# T32_ref.net
KiCad netlist of a schematic drawn in EAGLE
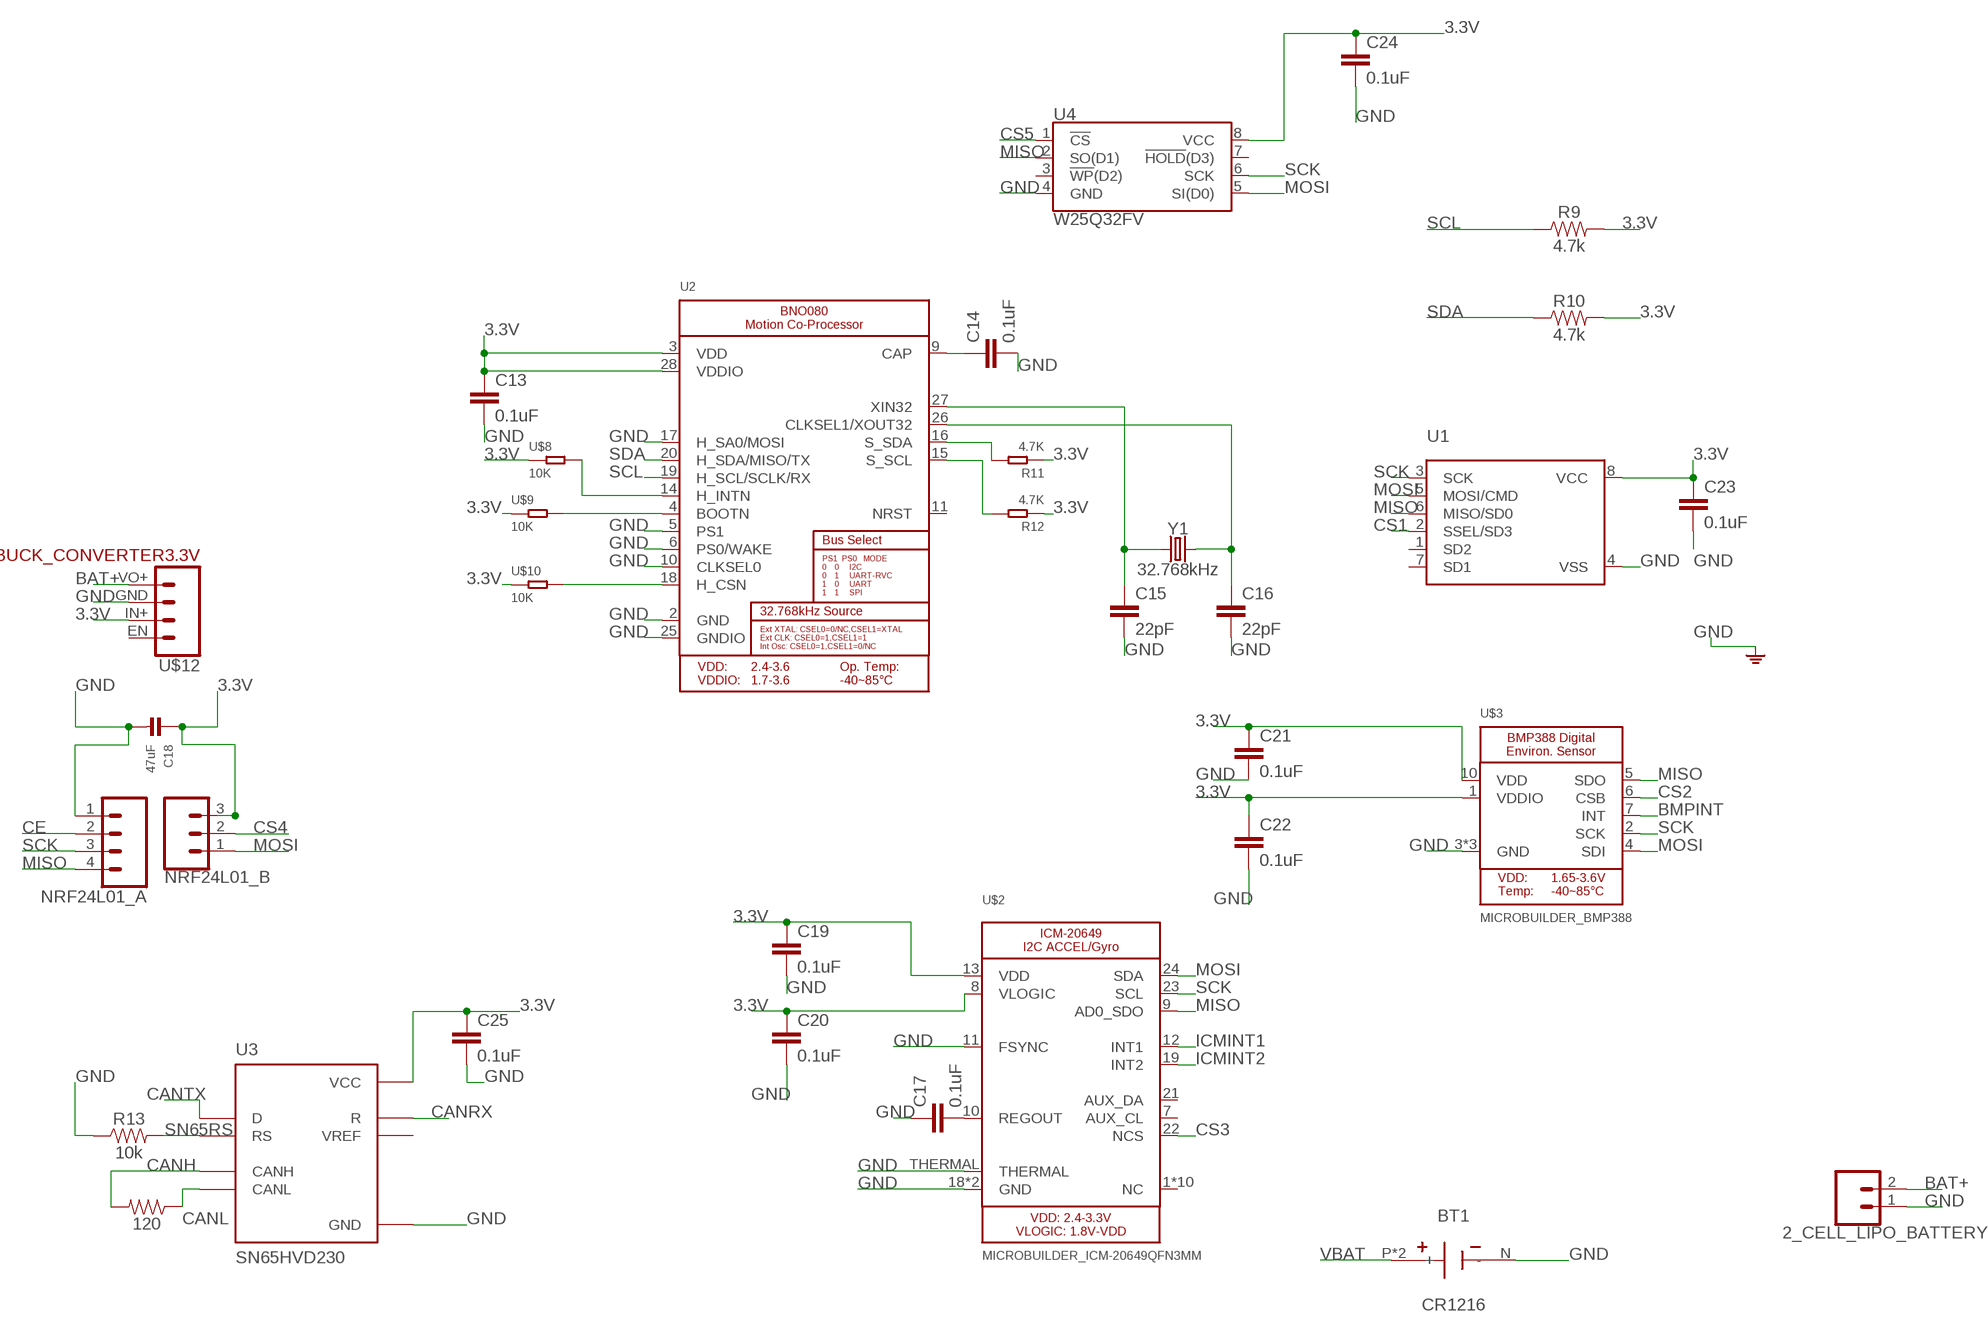
[diagram p0: schematic, sheet 1, part 1 of 2]
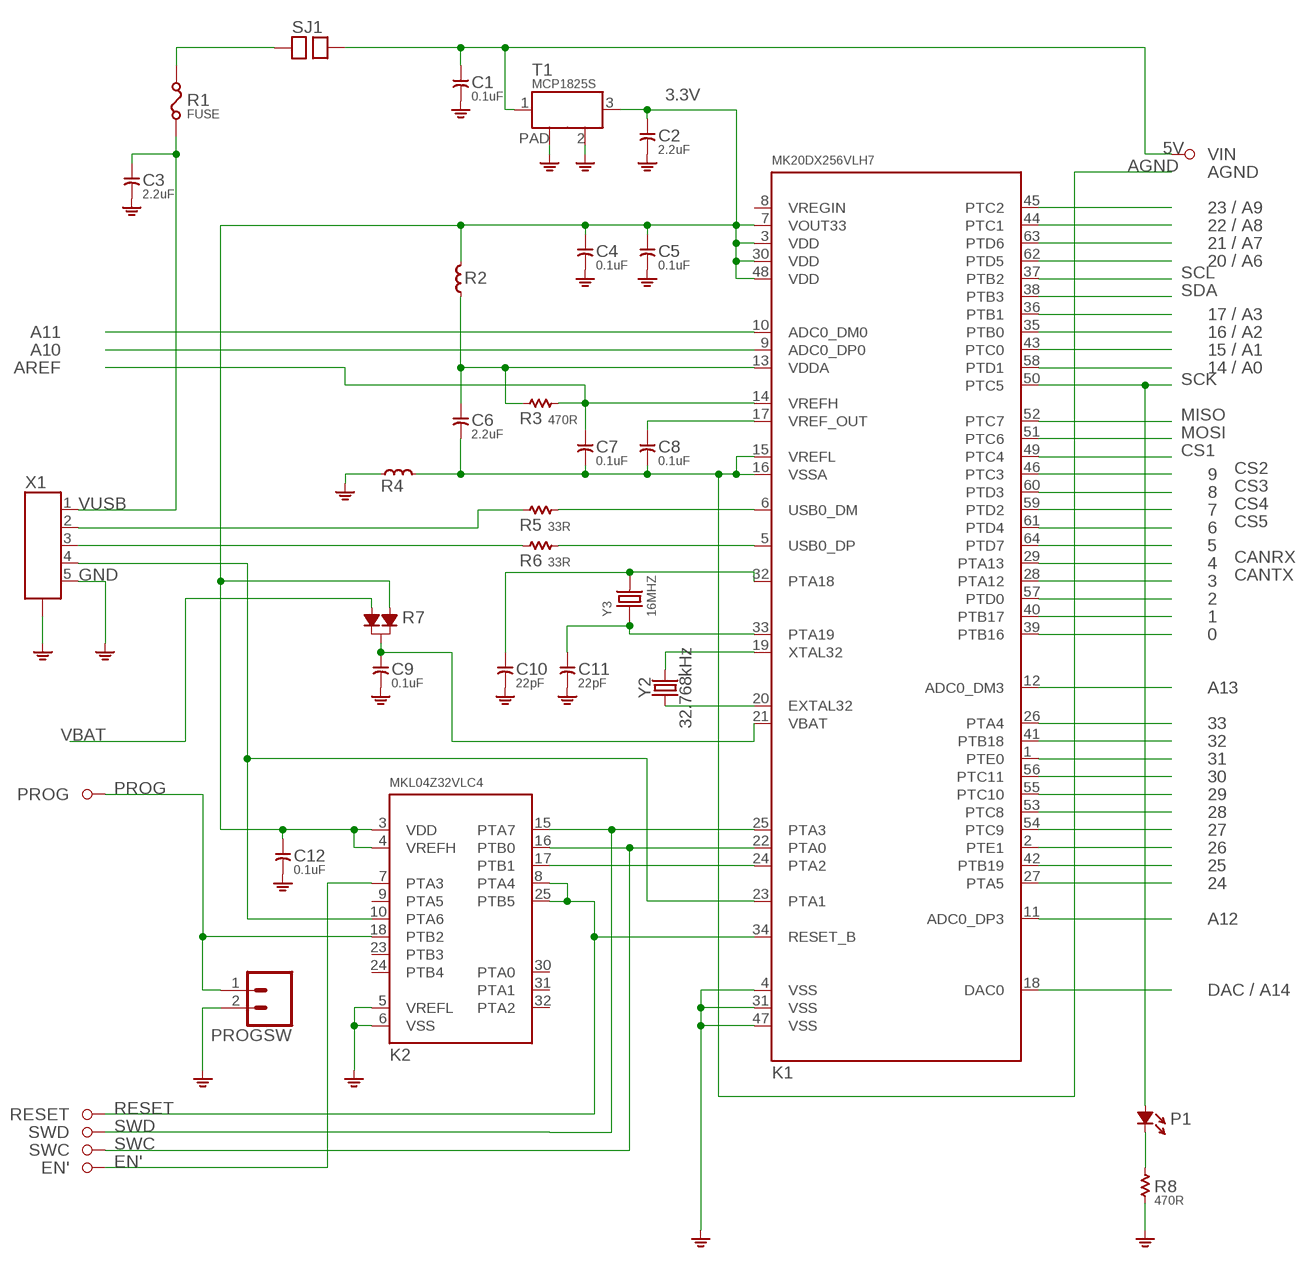
[diagram p1: schematic, sheet 1, part 2 of 2]

(export (version "E")
  (design (tool "Eeschema 10.0.6"))
  (components
    (comp (ref "2_CELL_LIPO_BATTERY")
      (value "CONN_02")
      (footprint "eagle-import:1X02")
      (libsource (lib "eagle-import") (part "CONN_02"))
    )
    (comp (ref "120")
      (value "RESISTOR1206")
      (footprint "eagle-import:1206")
      (libsource (lib "eagle-import") (part "RESISTOR1206"))
    )
    (comp (ref "BT1")
      (value "CR1216")
      (footprint "eagle-import:BAT_3000")
      (fields (field (name "MANUFACTURER") "Keystone Electronics") (field (name "MPN") "3000"))
      (libsource (lib "eagle-import") (part "COIN-CELL-SMT-3P-?-3000CR1216"))
    )
    (comp (ref "C1")
      (value "0.1uF")
      (footprint "eagle-import:C0603")
      (fields (field (name "MF") "Murata Electronics") (field (name "MPN") "GRM188R71C104KA01D"))
      (libsource (lib "eagle-import") (part "CAPACITOR-0.1UF"))
    )
    (comp (ref "C2")
      (value "2.2uF")
      (footprint "eagle-import:C0805")
      (fields (field (name "MF") "Taiyo Yuden") (field (name "MPN") "TMK212B7225KG-TR"))
      (libsource (lib "eagle-import") (part "CAPACITOR-2.2UF"))
    )
    (comp (ref "C3")
      (value "2.2uF")
      (footprint "eagle-import:C0805")
      (fields (field (name "MF") "Taiyo Yuden") (field (name "MPN") "TMK212B7225KG-TR"))
      (libsource (lib "eagle-import") (part "CAPACITOR-2.2UF"))
    )
    (comp (ref "C4")
      (value "0.1uF")
      (footprint "eagle-import:C0603")
      (fields (field (name "MF") "Murata Electronics") (field (name "MPN") "GRM188R71C104KA01D"))
      (libsource (lib "eagle-import") (part "CAPACITOR-0.1UF"))
    )
    (comp (ref "C5")
      (value "0.1uF")
      (footprint "eagle-import:C0603")
      (fields (field (name "MF") "Murata Electronics") (field (name "MPN") "GRM188R71C104KA01D"))
      (libsource (lib "eagle-import") (part "CAPACITOR-0.1UF"))
    )
    (comp (ref "C6")
      (value "2.2uF")
      (footprint "eagle-import:C0805")
      (fields (field (name "MF") "Taiyo Yuden") (field (name "MPN") "TMK212B7225KG-TR"))
      (libsource (lib "eagle-import") (part "CAPACITOR-2.2UF"))
    )
    (comp (ref "C7")
      (value "0.1uF")
      (footprint "eagle-import:C0603")
      (fields (field (name "MF") "Murata Electronics") (field (name "MPN") "GRM188R71C104KA01D"))
      (libsource (lib "eagle-import") (part "CAPACITOR-0.1UF"))
    )
    (comp (ref "C8")
      (value "0.1uF")
      (footprint "eagle-import:C0603")
      (fields (field (name "MF") "Murata Electronics") (field (name "MPN") "GRM188R71C104KA01D"))
      (libsource (lib "eagle-import") (part "CAPACITOR-0.1UF"))
    )
    (comp (ref "C9")
      (value "0.1uF")
      (footprint "eagle-import:C0603")
      (fields (field (name "MF") "Murata Electronics") (field (name "MPN") "GRM188R71C104KA01D"))
      (libsource (lib "eagle-import") (part "CAPACITOR-0.1UF"))
    )
    (comp (ref "C10")
      (value "22pF")
      (footprint "eagle-import:C0603")
      (fields (field (name "MF") "Vishay / Vitramon") (field (name "MPN") "VJ0603A220JXACW1BC"))
      (libsource (lib "eagle-import") (part "CAPACITOR-22PF"))
    )
    (comp (ref "C11")
      (value "22pF")
      (footprint "eagle-import:C0603")
      (fields (field (name "MF") "Vishay / Vitramon") (field (name "MPN") "VJ0603A220JXACW1BC"))
      (libsource (lib "eagle-import") (part "CAPACITOR-22PF"))
    )
    (comp (ref "C12")
      (value "0.1uF")
      (footprint "eagle-import:C0603")
      (fields (field (name "MF") "Murata Electronics") (field (name "MPN") "GRM188R71C104KA01D"))
      (libsource (lib "eagle-import") (part "CAPACITOR-0.1UF"))
    )
    (comp (ref "C13")
      (value "0.1uF")
      (footprint "eagle-import:0402")
      (libsource (lib "eagle-import") (part "0.1UF-0402-16V-10%"))
    )
    (comp (ref "C14")
      (value "0.1uF")
      (footprint "eagle-import:0402")
      (libsource (lib "eagle-import") (part "0.1UF-0402-16V-10%"))
    )
    (comp (ref "C15")
      (value "22pF")
      (footprint "eagle-import:0603")
      (libsource (lib "eagle-import") (part "22PF-0603-50V-5%"))
    )
    (comp (ref "C16")
      (value "22pF")
      (footprint "eagle-import:0603")
      (libsource (lib "eagle-import") (part "22PF-0603-50V-5%"))
    )
    (comp (ref "C17")
      (value "0.1uF")
      (footprint "eagle-import:0402")
      (libsource (lib "eagle-import") (part "0.1UF-0402-16V-10%"))
    )
    (comp (ref "C18")
      (value "47uF")
      (footprint "eagle-import:0805")
      (libsource (lib "eagle-import") (part "CAP_CERAMIC0805"))
    )
    (comp (ref "C19")
      (value "0.1uF")
      (footprint "eagle-import:0603")
      (libsource (lib "eagle-import") (part "0.1UF-0603-100V-10%"))
    )
    (comp (ref "C20")
      (value "0.1uF")
      (footprint "eagle-import:0603")
      (libsource (lib "eagle-import") (part "0.1UF-0603-100V-10%"))
    )
    (comp (ref "C21")
      (value "0.1uF")
      (footprint "eagle-import:0603")
      (libsource (lib "eagle-import") (part "0.1UF-0603-100V-10%"))
    )
    (comp (ref "C22")
      (value "0.1uF")
      (footprint "eagle-import:0603")
      (libsource (lib "eagle-import") (part "0.1UF-0603-100V-10%"))
    )
    (comp (ref "C23")
      (value "0.1uF")
      (footprint "eagle-import:0603")
      (libsource (lib "eagle-import") (part "0.1UF-0603-100V-10%"))
    )
    (comp (ref "C24")
      (value "0.1uF")
      (footprint "eagle-import:0603")
      (libsource (lib "eagle-import") (part "0.1UF-0603-100V-10%"))
    )
    (comp (ref "C25")
      (value "0.1uF")
      (footprint "eagle-import:0603")
      (libsource (lib "eagle-import") (part "0.1UF-0603-100V-10%"))
    )
    (comp (ref "K1")
      (value "MK20DX256VLH7")
      (footprint "eagle-import:LQFP64-05")
      (fields (field (name "MF") "NXP"))
      (libsource (lib "eagle-import") (part "MK20DX256VLH7"))
    )
    (comp (ref "K2")
      (value "MKL04Z32VLC4")
      (footprint "eagle-import:LQFP32-08")
      (fields (field (name "MF") "PJRC") (field (name "MPN") "IC_MKL04Z32_TQFP32"))
      (libsource (lib "eagle-import") (part "MKL04Z32VLC4"))
    )
    (comp (ref "NRF24L01_A")
      (value "CONN_04")
      (footprint "eagle-import:1X04")
      (libsource (lib "eagle-import") (part "CONN_04"))
    )
    (comp (ref "NRF24L01_B")
      (value "CONN_03")
      (footprint "eagle-import:1X03")
      (libsource (lib "eagle-import") (part "CONN_03"))
    )
    (comp (ref "P1")
      (value "LED")
      (footprint "eagle-import:LED-0805")
      (fields (field (name "MF") "ROHM Semiconductor") (field (name "MPN") "SML-211DTT86"))
      (libsource (lib "eagle-import") (part "LED"))
    )
    (comp (ref "PROGSW")
      (value "CONN_02")
      (footprint "eagle-import:1X02")
      (libsource (lib "eagle-import") (part "SparkFun-Connectors_513_CONN_02"))
    )
    (comp (ref "R1")
      (value "FUSE")
      (footprint "eagle-import:F0805")
      (fields (field (name "MF") "Bel Fuse") (field (name "MPN") "0ZCK0050FF2E"))
      (libsource (lib "eagle-import") (part "FUSE"))
    )
    (comp (ref "R2")
      (value "FERRITE")
      (footprint "eagle-import:L0603")
      (fields (field (name "MF") "Murata Electronics") (field (name "MPN") " BLM18AG601SN1D"))
      (libsource (lib "eagle-import") (part "FERRITE"))
    )
    (comp (ref "R3")
      (value "470R")
      (footprint "eagle-import:R0603")
      (fields (field (name "MF") "Vishay") (field (name "MPN") "CRCW0603470RFKEA"))
      (libsource (lib "eagle-import") (part "RESISTOR-470R"))
    )
    (comp (ref "R4")
      (value "FERRITE")
      (footprint "eagle-import:L0603")
      (fields (field (name "MF") "Murata Electronics") (field (name "MPN") " BLM18AG601SN1D"))
      (libsource (lib "eagle-import") (part "FERRITE"))
    )
    (comp (ref "R5")
      (value "33R")
      (footprint "eagle-import:R0603")
      (fields (field (name "MF") "Panasonic") (field (name "MPN") "ERJ-PA3F33R0V"))
      (libsource (lib "eagle-import") (part "RESISTOR-33R"))
    )
    (comp (ref "R6")
      (value "33R")
      (footprint "eagle-import:R0603")
      (fields (field (name "MF") "Panasonic") (field (name "MPN") "ERJ-PA3F33R0V"))
      (libsource (lib "eagle-import") (part "RESISTOR-33R"))
    )
    (comp (ref "R7")
      (value "DIODE_DUAL")
      (footprint "eagle-import:SOT-23")
      (fields (field (name "MF") "NXP Semiconductors") (field (name "MPN") "BAT54C,215"))
      (libsource (lib "eagle-import") (part "DIODE_DUAL"))
    )
    (comp (ref "R8")
      (value "470R")
      (footprint "eagle-import:R0603")
      (fields (field (name "MF") "Vishay") (field (name "MPN") "CRCW0603470RFKEA"))
      (libsource (lib "eagle-import") (part "RESISTOR-470R"))
    )
    (comp (ref "R9")
      (value "4.7k")
      (footprint "eagle-import:0603")
      (libsource (lib "eagle-import") (part "4.7KOHM-0603-1/10W-1%"))
    )
    (comp (ref "R10")
      (value "4.7k")
      (footprint "eagle-import:0603")
      (libsource (lib "eagle-import") (part "4.7KOHM-0603-1/10W-1%"))
    )
    (comp (ref "R11")
      (value "4.7K")
      (footprint "eagle-import:R0402")
      (fields (field (name "MPN") "RC0402JR-074K7L"))
      (libsource (lib "eagle-import") (part "SMD-RES-4.7K-5%-1/16W(0402)"))
    )
    (comp (ref "R12")
      (value "4.7K")
      (footprint "eagle-import:R0402")
      (fields (field (name "MPN") "RC0402JR-074K7L"))
      (libsource (lib "eagle-import") (part "SMD-RES-4.7K-5%-1/16W(0402)"))
    )
    (comp (ref "R13")
      (value "10k")
      (footprint "eagle-import:0603")
      (libsource (lib "eagle-import") (part "10KOHM-0603-1/10W-1%"))
    )
    (comp (ref "SJ1")
      (value "SOLDERJUMPER")
      (footprint "eagle-import:SOLDERJUMPER")
      (libsource (lib "eagle-import") (part "SOLDERJUMPER"))
    )
    (comp (ref "SX2")
      (value "PIN")
      (footprint "eagle-import:PTH_39MIL")
      (libsource (lib "eagle-import") (part "PIN"))
    )
    (comp (ref "SX38")
      (value "PIN")
      (footprint "eagle-import:PTH_39MIL")
      (libsource (lib "eagle-import") (part "PIN"))
    )
    (comp (ref "SX40")
      (value "PIN")
      (footprint "eagle-import:PTH_39MIL")
      (libsource (lib "eagle-import") (part "PIN"))
    )
    (comp (ref "SX57")
      (value "PIN")
      (footprint "eagle-import:PTH_39MIL")
      (libsource (lib "eagle-import") (part "PIN"))
    )
    (comp (ref "SX58")
      (value "PIN")
      (footprint "eagle-import:PTH_39MIL")
      (libsource (lib "eagle-import") (part "PIN"))
    )
    (comp (ref "SX59")
      (value "PIN")
      (footprint "eagle-import:PTH_39MIL")
      (libsource (lib "eagle-import") (part "PIN"))
    )
    (comp (ref "T1")
      (value "MCP1825S")
      (footprint "eagle-import:SOT-223")
      (fields (field (name "MF") "Microchip Technology") (field (name "MPN") "MCP1825S-3302E/DB"))
      (libsource (lib "eagle-import") (part "LDO"))
    )
    (comp (ref "U$2")
      (value "MICROBUILDER_ICM-20649QFN3MM")
      (footprint "eagle-import:MICROBUILDER_QFN24_3MM")
      (libsource (lib "eagle-import") (part "MICROBUILDER_ICM-20649QFN3MM"))
    )
    (comp (ref "U$3")
      (value "MICROBUILDER_BMP388")
      (footprint "eagle-import:MICROBUILDER_BMP388")
      (libsource (lib "eagle-import") (part "MICROBUILDER_BMP388"))
    )
    (comp (ref "U$8")
      (value "10K")
      (footprint "eagle-import:R0402")
      (fields (field (name "MPN") "RC0402JR-0710KL"))
      (libsource (lib "eagle-import") (part "SMD-RES-10K-5%-1/(0402)"))
    )
    (comp (ref "U$9")
      (value "10K")
      (footprint "eagle-import:R0402")
      (fields (field (name "MPN") "RC0402JR-0710KL"))
      (libsource (lib "eagle-import") (part "SMD-RES-10K-5%-1/(0402)"))
    )
    (comp (ref "U$10")
      (value "10K")
      (footprint "eagle-import:R0402")
      (fields (field (name "MPN") "RC0402JR-0710KL"))
      (libsource (lib "eagle-import") (part "SMD-RES-10K-5%-1/(0402)"))
    )
    (comp (ref "U$12")
      (value "BUCK_CONVERTER3.3V")
      (footprint "eagle-import:1X04")
      (fields (field (name "VOLTAGE") "3.3V"))
      (libsource (lib "eagle-import") (part "BUCK_CONVERTER3.3V"))
    )
    (comp (ref "U1")
      (value "MICROBUILDER_SMT_SDCARD_8PIN")
      (footprint "eagle-import:MICROBUILDER_LGA8_8X6")
      (libsource (lib "eagle-import") (part "MICROBUILDER_SMT_SDCARD_8PIN"))
    )
    (comp (ref "U2")
      (value "MICROBUILDER_BNO080")
      (footprint "eagle-import:MICROBUILDER_BNO080")
      (libsource (lib "eagle-import") (part "MICROBUILDER_BNO080"))
    )
    (comp (ref "U3")
      (value "SN65HVD230")
      (footprint "eagle-import:SOIC127P599X175-8N")
      (fields (field (name "MF") "Texas Instruments"))
      (libsource (lib "eagle-import") (part "SN65HVD230"))
    )
    (comp (ref "U4")
      (value "W25Q32FV")
      (footprint "eagle-import:WSON8-6X5MM")
      (libsource (lib "eagle-import") (part "W25Q32FVZP"))
    )
    (comp (ref "X1")
      (value "MINI-USB")
      (footprint "eagle-import:MOLEX_SD-67503-010")
      (fields (field (name "MF") "MOLEX") (field (name "MPN") "0675031020"))
      (libsource (lib "eagle-import") (part "MINI-USBMOLEX_0675031230"))
    )
    (comp (ref "Y1")
      (value "32.768kHz")
      (footprint "eagle-import:CRYSTAL-SMD-3.2X1.5MM")
      (libsource (lib "eagle-import") (part "CRYSTAL-32.768KHZSMD-3.2X1.5"))
    )
    (comp (ref "Y2")
      (value "32.768kHz")
      (footprint "eagle-import:CRYSTAL-SMD-3.2X1.5MM")
      (libsource (lib "eagle-import") (part "CRYSTAL-32.768KHZSMD-3.2X1.5"))
    )
    (comp (ref "Y3")
      (value "16MHZ")
      (footprint "eagle-import:X2-SMD-5.0X3.2X1.3MM")
      (fields (field (name "MPN") "X053201602002"))
      (libsource (lib "eagle-import") (part "SMD-CRYSTAL-16MHZ-8PF-20PPM-40R(2P-5.0X3.2MM)"))
    )
  )
  (nets
    (net (code "1") (name "/3.3V") (class "Default")
      (node (ref "C12") (pin "1") (pinfunction "1_1") (pintype "passive"))
      (node (ref "C13") (pin "1") (pinfunction "1_1") (pintype "passive"))
      (node (ref "C18") (pin "1") (pinfunction "P$1_1") (pintype "passive"))
      (node (ref "C19") (pin "1") (pinfunction "1_1") (pintype "passive"))
      (node (ref "C2") (pin "1") (pinfunction "1_1") (pintype "passive"))
      (node (ref "C20") (pin "1") (pinfunction "1_1") (pintype "passive"))
      (node (ref "C21") (pin "1") (pinfunction "1_1") (pintype "passive"))
      (node (ref "C22") (pin "1") (pinfunction "1_1") (pintype "passive"))
      (node (ref "C23") (pin "1") (pinfunction "1_1") (pintype "passive"))
      (node (ref "C24") (pin "1") (pinfunction "1_1") (pintype "passive"))
      (node (ref "C25") (pin "1") (pinfunction "1_1") (pintype "passive"))
      (node (ref "C4") (pin "1") (pinfunction "1_1") (pintype "passive"))
      (node (ref "C5") (pin "1") (pinfunction "1_1") (pintype "passive"))
      (node (ref "K1") (pin "3") (pinfunction "VDD_3") (pintype "bidirectional"))
      (node (ref "K1") (pin "30") (pinfunction "VDD_30") (pintype "bidirectional"))
      (node (ref "K1") (pin "48") (pinfunction "VDD_48") (pintype "bidirectional"))
      (node (ref "K1") (pin "7") (pinfunction "VOUT33_7") (pintype "bidirectional"))
      (node (ref "K2") (pin "3") (pinfunction "VDD_3") (pintype "bidirectional"))
      (node (ref "K2") (pin "4") (pinfunction "VREFH_4") (pintype "bidirectional"))
      (node (ref "NRF24L01_B") (pin "3") (pinfunction "3_3") (pintype "passive"))
      (node (ref "R10") (pin "2") (pinfunction "2_2") (pintype "passive"))
      (node (ref "R11") (pin "1") (pinfunction "1_1") (pintype "passive"))
      (node (ref "R12") (pin "1") (pinfunction "1_1") (pintype "passive"))
      (node (ref "R2") (pin "2") (pinfunction "2_2") (pintype "passive"))
      (node (ref "R7") (pin "1") (pinfunction "1_1") (pintype "bidirectional"))
      (node (ref "R9") (pin "2") (pinfunction "2_2") (pintype "passive"))
      (node (ref "T1") (pin "3") (pinfunction "OUT_3") (pintype "bidirectional"))
      (node (ref "U$10") (pin "1") (pinfunction "1_1") (pintype "passive"))
      (node (ref "U$12") (pin "IN+") (pinfunction "IN+_IN+") (pintype "passive"))
      (node (ref "U$2") (pin "13") (pinfunction "VDD_13") (pintype "power_in"))
      (node (ref "U$2") (pin "8") (pinfunction "VLOGIC_8") (pintype "power_in"))
      (node (ref "U$3") (pin "1") (pinfunction "VDDIO_1") (pintype "power_in"))
      (node (ref "U$3") (pin "10") (pinfunction "VDD_10") (pintype "power_in"))
      (node (ref "U$8") (pin "1") (pinfunction "1_1") (pintype "passive"))
      (node (ref "U$9") (pin "1") (pinfunction "1_1") (pintype "passive"))
      (node (ref "U1") (pin "8") (pinfunction "VCC_8") (pintype "power_in"))
      (node (ref "U2") (pin "28") (pinfunction "VDDIO_28") (pintype "power_in"))
      (node (ref "U2") (pin "3") (pinfunction "VDD_3") (pintype "power_in"))
      (node (ref "U3") (pin "3") (pinfunction "VCC_3") (pintype "power_in"))
      (node (ref "U4") (pin "8") (pinfunction "VCC_8") (pintype "bidirectional"))
    )
    (net (code "2") (name "/5V") (class "Default")
      (node (ref "C1") (pin "1") (pinfunction "1_1") (pintype "passive"))
      (node (ref "R1") (pin "2") (pinfunction "2_2") (pintype "bidirectional"))
      (node (ref "SJ1") (pin "1") (pinfunction "1_1") (pintype "passive"))
      (node (ref "SJ1") (pin "2") (pinfunction "2_2") (pintype "passive"))
      (node (ref "SX2") (pin "1") (pinfunction "P$1_1") (pintype "bidirectional"))
      (node (ref "T1") (pin "1") (pinfunction "IN_1") (pintype "bidirectional"))
    )
    (net (code "3") (name "/AGND") (class "Default")
      (node (ref "C6") (pin "2") (pinfunction "2_2") (pintype "passive"))
      (node (ref "C7") (pin "2") (pinfunction "2_2") (pintype "passive"))
      (node (ref "C8") (pin "2") (pinfunction "2_2") (pintype "passive"))
      (node (ref "K1") (pin "15") (pinfunction "VREFL_15") (pintype "bidirectional"))
      (node (ref "K1") (pin "16") (pinfunction "VSSA_16") (pintype "bidirectional"))
      (node (ref "R4") (pin "2") (pinfunction "2_2") (pintype "passive"))
    )
    (net (code "4") (name "/BAT+") (class "Default")
      (node (ref "2_CELL_LIPO_BATTERY") (pin "2") (pinfunction "2_2") (pintype "passive"))
      (node (ref "U$12") (pin "VO+") (pinfunction "VO+_VO+") (pintype "passive"))
    )
    (net (code "5") (name "/BMPINT") (class "Default")
      (node (ref "U$3") (pin "7") (pinfunction "INT_7") (pintype "output"))
    )
    (net (code "6") (name "/CANH") (class "Default")
      (node (ref "120") (pin "2") (pinfunction "2_2") (pintype "passive"))
      (node (ref "U3") (pin "7") (pinfunction "CANH_7") (pintype "bidirectional"))
    )
    (net (code "7") (name "/CANL") (class "Default")
      (node (ref "120") (pin "1") (pinfunction "1_1") (pintype "passive"))
      (node (ref "U3") (pin "6") (pinfunction "CANL_6") (pintype "bidirectional"))
    )
    (net (code "8") (name "/CANRX") (class "Default")
      (node (ref "K1") (pin "29") (pinfunction "PTA13_29") (pintype "bidirectional"))
      (node (ref "U3") (pin "4") (pinfunction "R_4") (pintype "output"))
    )
    (net (code "9") (name "/CANTX") (class "Default")
      (node (ref "K1") (pin "28") (pinfunction "PTA12_28") (pintype "bidirectional"))
      (node (ref "U3") (pin "1") (pinfunction "D_1") (pintype "input"))
    )
    (net (code "10") (name "/CE") (class "Default")
      (node (ref "NRF24L01_A") (pin "2") (pinfunction "2_2") (pintype "passive"))
    )
    (net (code "11") (name "/CS1") (class "Default")
      (node (ref "K1") (pin "49") (pinfunction "PTC4_49") (pintype "bidirectional"))
      (node (ref "U1") (pin "2") (pinfunction "SSEL/SD3_2") (pintype "bidirectional"))
    )
    (net (code "12") (name "/CS2") (class "Default")
      (node (ref "K1") (pin "46") (pinfunction "PTC3_46") (pintype "bidirectional"))
      (node (ref "U$3") (pin "6") (pinfunction "CSB_6") (pintype "input"))
    )
    (net (code "13") (name "/CS3") (class "Default")
      (node (ref "K1") (pin "60") (pinfunction "PTD3_60") (pintype "bidirectional"))
      (node (ref "U$2") (pin "22") (pinfunction "NCS_22") (pintype "input"))
    )
    (net (code "14") (name "/CS4") (class "Default")
      (node (ref "K1") (pin "59") (pinfunction "PTD2_59") (pintype "bidirectional"))
      (node (ref "NRF24L01_B") (pin "2") (pinfunction "2_2") (pintype "passive"))
    )
    (net (code "15") (name "/CS5") (class "Default")
      (node (ref "K1") (pin "61") (pinfunction "PTD4_61") (pintype "bidirectional"))
      (node (ref "U4") (pin "1") (pinfunction "~{CS}_1") (pintype "bidirectional"))
    )
    (net (code "16") (name "/EN'") (class "Default")
      (node (ref "K2") (pin "7") (pinfunction "PTA3_7") (pintype "bidirectional"))
      (node (ref "SX59") (pin "1") (pinfunction "P$1_1") (pintype "bidirectional"))
    )
    (net (code "17") (name "/ICMINT1") (class "Default")
      (node (ref "U$2") (pin "12") (pinfunction "INT1_12") (pintype "output"))
    )
    (net (code "18") (name "/ICMINT2") (class "Default")
      (node (ref "U$2") (pin "19") (pinfunction "INT2_19") (pintype "output"))
    )
    (net (code "19") (name "/MISO") (class "Default")
      (node (ref "K1") (pin "52") (pinfunction "PTC7_52") (pintype "bidirectional"))
      (node (ref "NRF24L01_A") (pin "4") (pinfunction "4_4") (pintype "passive"))
      (node (ref "U$2") (pin "9") (pinfunction "AD0_SDO_9") (pintype "input"))
      (node (ref "U$3") (pin "5") (pinfunction "SDO_5") (pintype "output"))
      (node (ref "U1") (pin "6") (pinfunction "MISO/SD0_6") (pintype "bidirectional"))
      (node (ref "U4") (pin "2") (pinfunction "SO(D1)_2") (pintype "bidirectional"))
    )
    (net (code "20") (name "/MOSI") (class "Default")
      (node (ref "K1") (pin "51") (pinfunction "PTC6_51") (pintype "bidirectional"))
      (node (ref "NRF24L01_B") (pin "1") (pinfunction "1_1") (pintype "passive"))
      (node (ref "U$2") (pin "24") (pinfunction "SDA_24") (pintype "bidirectional"))
      (node (ref "U$3") (pin "4") (pinfunction "SDI_4") (pintype "input"))
      (node (ref "U1") (pin "5") (pinfunction "MOSI/CMD_5") (pintype "bidirectional"))
      (node (ref "U4") (pin "5") (pinfunction "SI(D0)_5") (pintype "bidirectional"))
    )
    (net (code "21") (name "/PROG") (class "Default")
      (node (ref "K2") (pin "18") (pinfunction "PTB2_18") (pintype "bidirectional"))
      (node (ref "PROGSW") (pin "1") (pinfunction "1_1") (pintype "passive"))
      (node (ref "SX40") (pin "1") (pinfunction "P$1_1") (pintype "bidirectional"))
    )
    (net (code "22") (name "/RESET") (class "Default")
      (node (ref "K1") (pin "34") (pinfunction "RESET_B_34") (pintype "bidirectional"))
      (node (ref "K2") (pin "25") (pinfunction "PTB5_25") (pintype "bidirectional"))
      (node (ref "K2") (pin "8") (pinfunction "PTA4_8") (pintype "bidirectional"))
      (node (ref "SX38") (pin "1") (pinfunction "P$1_1") (pintype "bidirectional"))
    )
    (net (code "23") (name "/SCK") (class "Default")
      (node (ref "K1") (pin "50") (pinfunction "PTC5_50") (pintype "bidirectional"))
      (node (ref "NRF24L01_A") (pin "3") (pinfunction "3_3") (pintype "passive"))
      (node (ref "P1") (pin "+") (pinfunction "+_+") (pintype "passive"))
      (node (ref "U$2") (pin "23") (pinfunction "SCL_23") (pintype "bidirectional"))
      (node (ref "U$3") (pin "2") (pinfunction "SCK_2") (pintype "input"))
      (node (ref "U1") (pin "3") (pinfunction "SCK_3") (pintype "input"))
      (node (ref "U4") (pin "6") (pinfunction "SCK_6") (pintype "bidirectional"))
    )
    (net (code "24") (name "/SCL") (class "Default")
      (node (ref "K1") (pin "37") (pinfunction "PTB2_37") (pintype "bidirectional"))
      (node (ref "R9") (pin "1") (pinfunction "1_1") (pintype "passive"))
      (node (ref "U2") (pin "19") (pinfunction "H_SCL/SCLK/RX_19") (pintype "bidirectional"))
    )
    (net (code "25") (name "/SDA") (class "Default")
      (node (ref "K1") (pin "38") (pinfunction "PTB3_38") (pintype "bidirectional"))
      (node (ref "R10") (pin "1") (pinfunction "1_1") (pintype "passive"))
      (node (ref "U2") (pin "20") (pinfunction "H_SDA/MISO/TX_20") (pintype "bidirectional"))
    )
    (net (code "26") (name "/SN65RS") (class "Default")
      (node (ref "R13") (pin "2") (pinfunction "2_2") (pintype "passive"))
      (node (ref "U3") (pin "8") (pinfunction "RS_8") (pintype "input"))
    )
    (net (code "27") (name "/SWC") (class "Default")
      (node (ref "K1") (pin "22") (pinfunction "PTA0_22") (pintype "bidirectional"))
      (node (ref "K2") (pin "16") (pinfunction "PTB0_16") (pintype "bidirectional"))
      (node (ref "SX58") (pin "1") (pinfunction "P$1_1") (pintype "bidirectional"))
    )
    (net (code "28") (name "/SWD") (class "Default")
      (node (ref "K1") (pin "25") (pinfunction "PTA3_25") (pintype "bidirectional"))
      (node (ref "K2") (pin "15") (pinfunction "PTA7_15") (pintype "bidirectional"))
      (node (ref "SX57") (pin "1") (pinfunction "P$1_1") (pintype "bidirectional"))
    )
    (net (code "29") (name "/VBAT") (class "Default")
      (node (ref "BT1") (pin "P") (pinfunction "+_P") (pintype "bidirectional"))
      (node (ref "BT1") (pin "P1") (pinfunction "+_P1") (pintype "bidirectional"))
      (node (ref "R7") (pin "2") (pinfunction "2_2") (pintype "bidirectional"))
    )
    (net (code "30") (name "/VUSB") (class "Default")
      (node (ref "C3") (pin "1") (pinfunction "1_1") (pintype "passive"))
      (node (ref "R1") (pin "1") (pinfunction "1_1") (pintype "bidirectional"))
      (node (ref "X1") (pin "1") (pinfunction "1_1") (pintype "input"))
    )
    (net (code "31") (name "GND") (class "Default")
      (node (ref "2_CELL_LIPO_BATTERY") (pin "1") (pinfunction "1_1") (pintype "passive"))
      (node (ref "BT1") (pin "N") (pinfunction "-_N") (pintype "bidirectional"))
      (node (ref "C1") (pin "2") (pinfunction "2_2") (pintype "passive"))
      (node (ref "C10") (pin "2") (pinfunction "2_2") (pintype "passive"))
      (node (ref "C11") (pin "2") (pinfunction "2_2") (pintype "passive"))
      (node (ref "C12") (pin "2") (pinfunction "2_2") (pintype "passive"))
      (node (ref "C13") (pin "2") (pinfunction "2_2") (pintype "passive"))
      (node (ref "C14") (pin "2") (pinfunction "2_2") (pintype "passive"))
      (node (ref "C15") (pin "2") (pinfunction "2_2") (pintype "passive"))
      (node (ref "C16") (pin "2") (pinfunction "2_2") (pintype "passive"))
      (node (ref "C17") (pin "1") (pinfunction "1_1") (pintype "passive"))
      (node (ref "C18") (pin "2") (pinfunction "P$2_2") (pintype "passive"))
      (node (ref "C19") (pin "2") (pinfunction "2_2") (pintype "passive"))
      (node (ref "C2") (pin "2") (pinfunction "2_2") (pintype "passive"))
      (node (ref "C20") (pin "2") (pinfunction "2_2") (pintype "passive"))
      (node (ref "C21") (pin "2") (pinfunction "2_2") (pintype "passive"))
      (node (ref "C22") (pin "2") (pinfunction "2_2") (pintype "passive"))
      (node (ref "C23") (pin "2") (pinfunction "2_2") (pintype "passive"))
      (node (ref "C24") (pin "2") (pinfunction "2_2") (pintype "passive"))
      (node (ref "C25") (pin "2") (pinfunction "2_2") (pintype "passive"))
      (node (ref "C3") (pin "2") (pinfunction "2_2") (pintype "passive"))
      (node (ref "C4") (pin "2") (pinfunction "2_2") (pintype "passive"))
      (node (ref "C5") (pin "2") (pinfunction "2_2") (pintype "passive"))
      (node (ref "C9") (pin "2") (pinfunction "2_2") (pintype "passive"))
      (node (ref "K1") (pin "31") (pinfunction "VSS_31") (pintype "bidirectional"))
      (node (ref "K1") (pin "4") (pinfunction "VSS_4") (pintype "bidirectional"))
      (node (ref "K1") (pin "47") (pinfunction "VSS_47") (pintype "bidirectional"))
      (node (ref "K2") (pin "5") (pinfunction "VREFL_5") (pintype "bidirectional"))
      (node (ref "K2") (pin "6") (pinfunction "VSS_6") (pintype "bidirectional"))
      (node (ref "NRF24L01_A") (pin "1") (pinfunction "1_1") (pintype "passive"))
      (node (ref "PROGSW") (pin "2") (pinfunction "2_2") (pintype "passive"))
      (node (ref "R13") (pin "1") (pinfunction "1_1") (pintype "passive"))
      (node (ref "R4") (pin "1") (pinfunction "1_1") (pintype "passive"))
      (node (ref "R8") (pin "1") (pinfunction "1_1") (pintype "passive"))
      (node (ref "T1") (pin "2") (pinfunction "GND_2") (pintype "bidirectional"))
      (node (ref "T1") (pin "PAD") (pinfunction "PAD_PAD") (pintype "bidirectional"))
      (node (ref "U$12") (pin "GND") (pinfunction "GND_GND") (pintype "passive"))
      (node (ref "U$2") (pin "11") (pinfunction "FSYNC_11") (pintype "input"))
      (node (ref "U$2") (pin "18") (pinfunction "GND_18") (pintype "power_in"))
      (node (ref "U$2") (pin "20") (pinfunction "GND_20") (pintype "power_in"))
      (node (ref "U$2") (pin "THERMAL") (pinfunction "THERMAL_THERMAL") (pintype "power_in"))
      (node (ref "U$3") (pin "3") (pinfunction "GND_3") (pintype "power_in"))
      (node (ref "U$3") (pin "8") (pinfunction "GND_8") (pintype "power_in"))
      (node (ref "U$3") (pin "9") (pinfunction "GND_9") (pintype "power_in"))
      (node (ref "U1") (pin "4") (pinfunction "VSS_4") (pintype "power_in"))
      (node (ref "U2") (pin "10") (pinfunction "CLKSEL0_10") (pintype "input"))
      (node (ref "U2") (pin "17") (pinfunction "H_SA0/MOSI_17") (pintype "output"))
      (node (ref "U2") (pin "2") (pinfunction "GND_2") (pintype "power_in"))
      (node (ref "U2") (pin "25") (pinfunction "GNDIO_25") (pintype "power_in"))
      (node (ref "U2") (pin "5") (pinfunction "PS1_5") (pintype "input"))
      (node (ref "U2") (pin "6") (pinfunction "PS0/WAKE_6") (pintype "input"))
      (node (ref "U3") (pin "2") (pinfunction "GND_2") (pintype "power_in"))
      (node (ref "U4") (pin "4") (pinfunction "GND_4") (pintype "bidirectional"))
      (node (ref "X1") (pin "5") (pinfunction "5_5") (pintype "input"))
      (node (ref "X1") (pin "P$1") (pinfunction "CASE_P$1") (pintype "input"))
      (node (ref "X1") (pin "P$2") (pinfunction "CASE_P$2") (pintype "input"))
      (node (ref "X1") (pin "P$3") (pinfunction "CASE_P$3") (pintype "input"))
      (node (ref "X1") (pin "P$4") (pinfunction "CASE_P$4") (pintype "input"))
      (node (ref "X1") (pin "P$5") (pinfunction "CASE_P$5") (pintype "input"))
      (node (ref "X1") (pin "P$6") (pinfunction "CASE_P$6") (pintype "input"))
    )
    (net (code "32") (name "Net-(K1-EXTAL32)") (class "Default")
      (node (ref "K1") (pin "20") (pinfunction "EXTAL32_20") (pintype "bidirectional"))
      (node (ref "Y2") (pin "P$1") (pinfunction "1_P$1") (pintype "passive"))
    )
    (net (code "33") (name "Net-(K1-PTA1)") (class "Default")
      (node (ref "K1") (pin "23") (pinfunction "PTA1_23") (pintype "bidirectional"))
      (node (ref "K2") (pin "10") (pinfunction "PTA6_10") (pintype "bidirectional"))
      (node (ref "X1") (pin "4") (pinfunction "4_4") (pintype "input"))
    )
    (net (code "34") (name "Net-(K1-PTA2)") (class "Default")
      (node (ref "K1") (pin "24") (pinfunction "PTA2_24") (pintype "bidirectional"))
      (node (ref "K2") (pin "17") (pinfunction "PTB1_17") (pintype "bidirectional"))
    )
    (net (code "35") (name "Net-(K1-PTA18)") (class "Default")
      (node (ref "C10") (pin "1") (pinfunction "1_1") (pintype "passive"))
      (node (ref "K1") (pin "32") (pinfunction "PTA18_32") (pintype "bidirectional"))
      (node (ref "Y3") (pin "2") (pinfunction "2_2") (pintype "passive"))
    )
    (net (code "36") (name "Net-(K1-PTA19)") (class "Default")
      (node (ref "C11") (pin "1") (pinfunction "1_1") (pintype "passive"))
      (node (ref "K1") (pin "33") (pinfunction "PTA19_33") (pintype "bidirectional"))
      (node (ref "Y3") (pin "1") (pinfunction "1_1") (pintype "passive"))
    )
    (net (code "37") (name "Net-(K1-USB0_DM)") (class "Default")
      (node (ref "K1") (pin "6") (pinfunction "USB0_DM_6") (pintype "bidirectional"))
      (node (ref "R5") (pin "2") (pinfunction "2_2") (pintype "passive"))
    )
    (net (code "38") (name "Net-(K1-USB0_DP)") (class "Default")
      (node (ref "K1") (pin "5") (pinfunction "USB0_DP_5") (pintype "bidirectional"))
      (node (ref "R6") (pin "2") (pinfunction "2_2") (pintype "passive"))
    )
    (net (code "39") (name "Net-(K1-VBAT)") (class "Default")
      (node (ref "C9") (pin "1") (pinfunction "1_1") (pintype "passive"))
      (node (ref "K1") (pin "21") (pinfunction "VBAT_21") (pintype "bidirectional"))
      (node (ref "R7") (pin "3") (pinfunction "3_3") (pintype "bidirectional"))
    )
    (net (code "40") (name "Net-(K1-VDDA)") (class "Default")
      (node (ref "C6") (pin "1") (pinfunction "1_1") (pintype "passive"))
      (node (ref "K1") (pin "13") (pinfunction "VDDA_13") (pintype "bidirectional"))
      (node (ref "R2") (pin "1") (pinfunction "1_1") (pintype "passive"))
      (node (ref "R3") (pin "1") (pinfunction "1_1") (pintype "passive"))
    )
    (net (code "41") (name "Net-(K1-VREFH)") (class "Default")
      (node (ref "C7") (pin "1") (pinfunction "1_1") (pintype "passive"))
      (node (ref "K1") (pin "14") (pinfunction "VREFH_14") (pintype "bidirectional"))
      (node (ref "R3") (pin "2") (pinfunction "2_2") (pintype "passive"))
    )
    (net (code "42") (name "Net-(K1-VREF_OUT)") (class "Default")
      (node (ref "C8") (pin "1") (pinfunction "1_1") (pintype "passive"))
      (node (ref "K1") (pin "17") (pinfunction "VREF_OUT_17") (pintype "bidirectional"))
    )
    (net (code "43") (name "Net-(K1-XTAL32)") (class "Default")
      (node (ref "K1") (pin "19") (pinfunction "XTAL32_19") (pintype "bidirectional"))
      (node (ref "Y2") (pin "P$2") (pinfunction "2_P$2") (pintype "passive"))
    )
    (net (code "44") (name "Net-(P1-Pad-)") (class "Default")
      (node (ref "P1") (pin "-") (pinfunction "-_-") (pintype "passive"))
      (node (ref "R8") (pin "2") (pinfunction "2_2") (pintype "passive"))
    )
    (net (code "45") (name "Net-(R5-Pad1)") (class "Default")
      (node (ref "R5") (pin "1") (pinfunction "1_1") (pintype "passive"))
      (node (ref "X1") (pin "2") (pinfunction "2_2") (pintype "input"))
    )
    (net (code "46") (name "Net-(R6-Pad1)") (class "Default")
      (node (ref "R6") (pin "1") (pinfunction "1_1") (pintype "passive"))
      (node (ref "X1") (pin "3") (pinfunction "3_3") (pintype "input"))
    )
    (net (code "47") (name "Net-(U$2-REGOUT)") (class "Default")
      (node (ref "C17") (pin "2") (pinfunction "2_2") (pintype "passive"))
      (node (ref "U$2") (pin "10") (pinfunction "REGOUT_10") (pintype "passive"))
    )
    (net (code "48") (name "Net-(U2-BOOTN)") (class "Default")
      (node (ref "U$9") (pin "2") (pinfunction "2_2") (pintype "passive"))
      (node (ref "U2") (pin "4") (pinfunction "BOOTN_4") (pintype "input"))
    )
    (net (code "49") (name "Net-(U2-CAP)") (class "Default")
      (node (ref "C14") (pin "1") (pinfunction "1_1") (pintype "passive"))
      (node (ref "U2") (pin "9") (pinfunction "CAP_9") (pintype "passive"))
    )
    (net (code "50") (name "Net-(U2-CLKSEL1{slash}XOUT32)") (class "Default")
      (node (ref "C16") (pin "1") (pinfunction "1_1") (pintype "passive"))
      (node (ref "U2") (pin "26") (pinfunction "CLKSEL1/XOUT32_26") (pintype "output"))
      (node (ref "Y1") (pin "P$2") (pinfunction "2_P$2") (pintype "passive"))
    )
    (net (code "51") (name "Net-(U2-H_CSN)") (class "Default")
      (node (ref "U$10") (pin "2") (pinfunction "2_2") (pintype "passive"))
      (node (ref "U2") (pin "18") (pinfunction "H_CSN_18") (pintype "input"))
    )
    (net (code "52") (name "Net-(U2-H_INTN)") (class "Default")
      (node (ref "U$8") (pin "2") (pinfunction "2_2") (pintype "passive"))
      (node (ref "U2") (pin "14") (pinfunction "H_INTN_14") (pintype "output"))
    )
    (net (code "53") (name "Net-(U2-S_SCL)") (class "Default")
      (node (ref "R12") (pin "2") (pinfunction "2_2") (pintype "passive"))
      (node (ref "U2") (pin "15") (pinfunction "S_SCL_15") (pintype "bidirectional"))
    )
    (net (code "54") (name "Net-(U2-S_SDA)") (class "Default")
      (node (ref "R11") (pin "2") (pinfunction "2_2") (pintype "passive"))
      (node (ref "U2") (pin "16") (pinfunction "S_SDA_16") (pintype "bidirectional"))
    )
    (net (code "55") (name "Net-(U2-XIN32)") (class "Default")
      (node (ref "C15") (pin "1") (pinfunction "1_1") (pintype "passive"))
      (node (ref "U2") (pin "27") (pinfunction "XIN32_27") (pintype "input"))
      (node (ref "Y1") (pin "P$1") (pinfunction "1_P$1") (pintype "passive"))
    )
    (net (code "56") (name "unconnected-(K1-ADC0_DM0-Pad10)") (class "Default")
      (node (ref "K1") (pin "10") (pinfunction "ADC0_DM0_10") (pintype "bidirectional"))
    )
    (net (code "57") (name "unconnected-(K1-ADC0_DM3-Pad12)") (class "Default")
      (node (ref "K1") (pin "12") (pinfunction "ADC0_DM3_12") (pintype "bidirectional"))
    )
    (net (code "58") (name "unconnected-(K1-ADC0_DP0-Pad9)") (class "Default")
      (node (ref "K1") (pin "9") (pinfunction "ADC0_DP0_9") (pintype "bidirectional"))
    )
    (net (code "59") (name "unconnected-(K1-ADC0_DP3-Pad11)") (class "Default")
      (node (ref "K1") (pin "11") (pinfunction "ADC0_DP3_11") (pintype "bidirectional"))
    )
    (net (code "60") (name "unconnected-(K1-DAC0-Pad18)") (class "Default")
      (node (ref "K1") (pin "18") (pinfunction "DAC0_18") (pintype "bidirectional"))
    )
    (net (code "61") (name "unconnected-(K1-PTA4-Pad26)") (class "Default")
      (node (ref "K1") (pin "26") (pinfunction "PTA4_26") (pintype "bidirectional"))
    )
    (net (code "62") (name "unconnected-(K1-PTA5-Pad27)") (class "Default")
      (node (ref "K1") (pin "27") (pinfunction "PTA5_27") (pintype "bidirectional"))
    )
    (net (code "63") (name "unconnected-(K1-PTB0-Pad35)") (class "Default")
      (node (ref "K1") (pin "35") (pinfunction "PTB0_35") (pintype "bidirectional"))
    )
    (net (code "64") (name "unconnected-(K1-PTB1-Pad36)") (class "Default")
      (node (ref "K1") (pin "36") (pinfunction "PTB1_36") (pintype "bidirectional"))
    )
    (net (code "65") (name "unconnected-(K1-PTB16-Pad39)") (class "Default")
      (node (ref "K1") (pin "39") (pinfunction "PTB16_39") (pintype "bidirectional"))
    )
    (net (code "66") (name "unconnected-(K1-PTB17-Pad40)") (class "Default")
      (node (ref "K1") (pin "40") (pinfunction "PTB17_40") (pintype "bidirectional"))
    )
    (net (code "67") (name "unconnected-(K1-PTB18-Pad41)") (class "Default")
      (node (ref "K1") (pin "41") (pinfunction "PTB18_41") (pintype "bidirectional"))
    )
    (net (code "68") (name "unconnected-(K1-PTB19-Pad42)") (class "Default")
      (node (ref "K1") (pin "42") (pinfunction "PTB19_42") (pintype "bidirectional"))
    )
    (net (code "69") (name "unconnected-(K1-PTC0-Pad43)") (class "Default")
      (node (ref "K1") (pin "43") (pinfunction "PTC0_43") (pintype "bidirectional"))
    )
    (net (code "70") (name "unconnected-(K1-PTC1-Pad44)") (class "Default")
      (node (ref "K1") (pin "44") (pinfunction "PTC1_44") (pintype "bidirectional"))
    )
    (net (code "71") (name "unconnected-(K1-PTC2-Pad45)") (class "Default")
      (node (ref "K1") (pin "45") (pinfunction "PTC2_45") (pintype "bidirectional"))
    )
    (net (code "72") (name "unconnected-(K1-PTC8-Pad53)") (class "Default")
      (node (ref "K1") (pin "53") (pinfunction "PTC8_53") (pintype "bidirectional"))
    )
    (net (code "73") (name "unconnected-(K1-PTC9-Pad54)") (class "Default")
      (node (ref "K1") (pin "54") (pinfunction "PTC9_54") (pintype "bidirectional"))
    )
    (net (code "74") (name "unconnected-(K1-PTC10-Pad55)") (class "Default")
      (node (ref "K1") (pin "55") (pinfunction "PTC10_55") (pintype "bidirectional"))
    )
    (net (code "75") (name "unconnected-(K1-PTC11-Pad56)") (class "Default")
      (node (ref "K1") (pin "56") (pinfunction "PTC11_56") (pintype "bidirectional"))
    )
    (net (code "76") (name "unconnected-(K1-PTD0-Pad57)") (class "Default")
      (node (ref "K1") (pin "57") (pinfunction "PTD0_57") (pintype "bidirectional"))
    )
    (net (code "77") (name "unconnected-(K1-PTD1-Pad58)") (class "Default")
      (node (ref "K1") (pin "58") (pinfunction "PTD1_58") (pintype "bidirectional"))
    )
    (net (code "78") (name "unconnected-(K1-PTD5-Pad62)") (class "Default")
      (node (ref "K1") (pin "62") (pinfunction "PTD5_62") (pintype "bidirectional"))
    )
    (net (code "79") (name "unconnected-(K1-PTD6-Pad63)") (class "Default")
      (node (ref "K1") (pin "63") (pinfunction "PTD6_63") (pintype "bidirectional"))
    )
    (net (code "80") (name "unconnected-(K1-PTD7-Pad64)") (class "Default")
      (node (ref "K1") (pin "64") (pinfunction "PTD7_64") (pintype "bidirectional"))
    )
    (net (code "81") (name "unconnected-(K1-PTE0-Pad1)") (class "Default")
      (node (ref "K1") (pin "1") (pinfunction "PTE0_1") (pintype "bidirectional"))
    )
    (net (code "82") (name "unconnected-(K1-PTE1-Pad2)") (class "Default")
      (node (ref "K1") (pin "2") (pinfunction "PTE1_2") (pintype "bidirectional"))
    )
    (net (code "83") (name "unconnected-(K1-VREGIN-Pad8)") (class "Default")
      (node (ref "K1") (pin "8") (pinfunction "VREGIN_8") (pintype "bidirectional"))
    )
    (net (code "84") (name "unconnected-(K2-PTA0-Pad30)") (class "Default")
      (node (ref "K2") (pin "30") (pinfunction "PTA0_30") (pintype "bidirectional"))
    )
    (net (code "85") (name "unconnected-(K2-PTA1-Pad31)") (class "Default")
      (node (ref "K2") (pin "31") (pinfunction "PTA1_31") (pintype "bidirectional"))
    )
    (net (code "86") (name "unconnected-(K2-PTA2-Pad32)") (class "Default")
      (node (ref "K2") (pin "32") (pinfunction "PTA2_32") (pintype "bidirectional"))
    )
    (net (code "87") (name "unconnected-(K2-PTA5-Pad9)") (class "Default")
      (node (ref "K2") (pin "9") (pinfunction "PTA5_9") (pintype "bidirectional"))
    )
    (net (code "88") (name "unconnected-(K2-PTB3-Pad23)") (class "Default")
      (node (ref "K2") (pin "23") (pinfunction "PTB3_23") (pintype "bidirectional"))
    )
    (net (code "89") (name "unconnected-(K2-PTB4-Pad24)") (class "Default")
      (node (ref "K2") (pin "24") (pinfunction "PTB4_24") (pintype "bidirectional"))
    )
    (net (code "90") (name "unconnected-(U$2-AUX_CL-Pad7)") (class "Default")
      (node (ref "U$2") (pin "7") (pinfunction "AUX_CL_7") (pintype "bidirectional"))
    )
    (net (code "91") (name "unconnected-(U$2-AUX_DA-Pad21)") (class "Default")
      (node (ref "U$2") (pin "21") (pinfunction "AUX_DA_21") (pintype "bidirectional"))
    )
    (net (code "92") (name "unconnected-(U$2-NC-Pad1)") (class "Default")
      (node (ref "U$2") (pin "1") (pinfunction "NC_1") (pintype "no_connect"))
    )
    (net (code "93") (name "unconnected-(U$2-NC-Pad2)") (class "Default")
      (node (ref "U$2") (pin "2") (pinfunction "NC_2") (pintype "no_connect"))
    )
    (net (code "94") (name "unconnected-(U$2-NC-Pad3)") (class "Default")
      (node (ref "U$2") (pin "3") (pinfunction "NC_3") (pintype "no_connect"))
    )
    (net (code "95") (name "unconnected-(U$2-NC-Pad4)") (class "Default")
      (node (ref "U$2") (pin "4") (pinfunction "NC_4") (pintype "no_connect"))
    )
    (net (code "96") (name "unconnected-(U$2-NC-Pad5)") (class "Default")
      (node (ref "U$2") (pin "5") (pinfunction "NC_5") (pintype "no_connect"))
    )
    (net (code "97") (name "unconnected-(U$2-NC-Pad6)") (class "Default")
      (node (ref "U$2") (pin "6") (pinfunction "NC_6") (pintype "no_connect"))
    )
    (net (code "98") (name "unconnected-(U$2-NC-Pad14)") (class "Default")
      (node (ref "U$2") (pin "14") (pinfunction "NC_14") (pintype "no_connect"))
    )
    (net (code "99") (name "unconnected-(U$2-NC-Pad15)") (class "Default")
      (node (ref "U$2") (pin "15") (pinfunction "NC_15") (pintype "no_connect"))
    )
    (net (code "100") (name "unconnected-(U$2-NC-Pad16)") (class "Default")
      (node (ref "U$2") (pin "16") (pinfunction "NC_16") (pintype "no_connect"))
    )
    (net (code "101") (name "unconnected-(U$2-NC-Pad17)") (class "Default")
      (node (ref "U$2") (pin "17") (pinfunction "NC_17") (pintype "no_connect"))
    )
    (net (code "102") (name "unconnected-(U$12-PadEN)") (class "Default")
      (node (ref "U$12") (pin "EN") (pinfunction "EN_EN") (pintype "passive"))
    )
    (net (code "103") (name "unconnected-(U1-SD1-Pad7)") (class "Default")
      (node (ref "U1") (pin "7") (pinfunction "SD1_7") (pintype "bidirectional"))
    )
    (net (code "104") (name "unconnected-(U1-SD2-Pad1)") (class "Default")
      (node (ref "U1") (pin "1") (pinfunction "SD2_1") (pintype "bidirectional"))
    )
    (net (code "105") (name "unconnected-(U2-NRST-Pad11)") (class "Default")
      (node (ref "U2") (pin "11") (pinfunction "NRST_11") (pintype "input"))
    )
    (net (code "106") (name "unconnected-(U3-VREF-Pad5)") (class "Default")
      (node (ref "U3") (pin "5") (pinfunction "VREF_5") (pintype "output"))
    )
    (net (code "107") (name "unconnected-(U4-~{HOLD}(D3)-Pad7)") (class "Default")
      (node (ref "U4") (pin "7") (pinfunction "~{HOLD}(D3)_7") (pintype "bidirectional"))
    )
    (net (code "108") (name "unconnected-(U4-~{WP}(D2)-Pad3)") (class "Default")
      (node (ref "U4") (pin "3") (pinfunction "~{WP}(D2)_3") (pintype "bidirectional"))
    )
  )
)
